# MD2_SE_Main_rev4_1.net
KiCad netlist of a schematic drawn in EAGLE
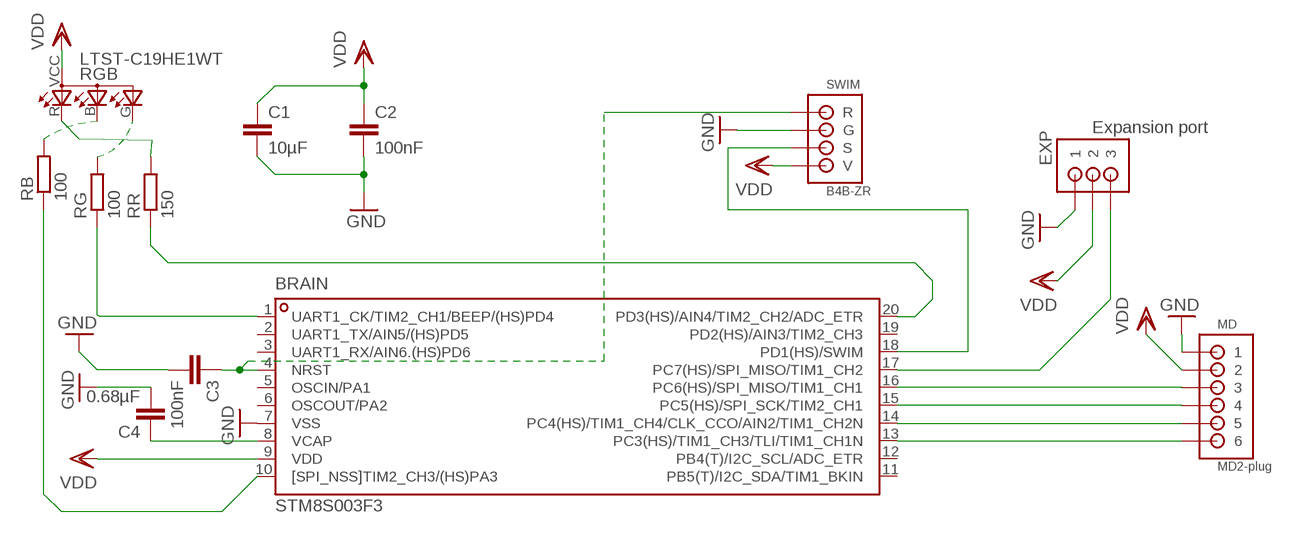
[diagram p0: schematic, sheet 1]

(export (version "E")
  (design (tool "Eeschema 10.0.6"))
  (components
    (comp (ref "BRAIN")
      (value "STM8S003F3")
      (footprint "eagle-import:TSSOP20")
      (libsource (lib "eagle-import") (part "STM8S003F3"))
    )
    (comp (ref "C1")
      (value "10µF")
      (footprint "eagle-import:C0603K")
      (libsource (lib "eagle-import") (part "C-EUC0603K"))
    )
    (comp (ref "C2")
      (value "100nF")
      (footprint "eagle-import:C0603K")
      (libsource (lib "eagle-import") (part "C-EUC0603K"))
    )
    (comp (ref "C3")
      (value "100nF")
      (footprint "eagle-import:C0603K")
      (libsource (lib "eagle-import") (part "C-EUC0603K"))
    )
    (comp (ref "C4")
      (value "0.68µF")
      (footprint "eagle-import:C0603K")
      (libsource (lib "eagle-import") (part "C-EUC0603K"))
    )
    (comp (ref "EXP")
      (value "Expansion port")
      (footprint "eagle-import:B3B-ZR")
      (libsource (lib "eagle-import") (part "B3B-ZR"))
    )
    (comp (ref "MD")
      (value "MD2-plug")
      (footprint "eagle-import:B6B-ZR")
      (libsource (lib "eagle-import") (part "B6B-ZR"))
    )
    (comp (ref "RB")
      (value "100")
      (footprint "eagle-import:R0603")
      (libsource (lib "eagle-import") (part "R-EU_R0603"))
    )
    (comp (ref "RG")
      (value "100")
      (footprint "eagle-import:R0603")
      (libsource (lib "eagle-import") (part "R-EU_R0603"))
    )
    (comp (ref "RGB")
      (value "LTST-C19HE1WT")
      (footprint "eagle-import:0606")
      (libsource (lib "eagle-import") (part "LTST-C19HE1WT"))
    )
    (comp (ref "RR")
      (value "150")
      (footprint "eagle-import:R0603")
      (libsource (lib "eagle-import") (part "R-EU_R0603"))
    )
    (comp (ref "SWIM")
      (value "B4B-ZR")
      (footprint "eagle-import:B4B-ZR")
      (libsource (lib "eagle-import") (part "B4B-ZR"))
    )
  )
  (nets
    (net (code "1") (name "GND") (class "Default")
      (node (ref "BRAIN") (pin "7") (pinfunction "VSS_7") (pintype "bidirectional"))
      (node (ref "C1") (pin "2") (pinfunction "2_2") (pintype "passive"))
      (node (ref "C2") (pin "2") (pinfunction "2_2") (pintype "passive"))
      (node (ref "C3") (pin "2") (pinfunction "2_2") (pintype "passive"))
      (node (ref "C4") (pin "2") (pinfunction "2_2") (pintype "passive"))
      (node (ref "EXP") (pin "1") (pinfunction "1_1") (pintype "bidirectional"))
      (node (ref "MD") (pin "1") (pinfunction "1_1") (pintype "bidirectional"))
      (node (ref "SWIM") (pin "GND") (pinfunction "G_GND") (pintype "bidirectional"))
    )
    (net (code "2") (name "Net-(BRAIN-NRST)") (class "Default")
      (node (ref "BRAIN") (pin "4") (pinfunction "NRST_4") (pintype "input"))
      (node (ref "C3") (pin "1") (pinfunction "1_1") (pintype "passive"))
      (node (ref "SWIM") (pin "RST") (pinfunction "R_RST") (pintype "bidirectional"))
    )
    (net (code "3") (name "Net-(BRAIN-PC3(HS){slash}TIM1_CH3{slash}TLI{slash}TIM1_CH1N)") (class "Default")
      (node (ref "BRAIN") (pin "13") (pinfunction "PC3(HS)/TIM1_CH3/TLI/TIM1_CH1N_13") (pintype "bidirectional"))
      (node (ref "MD") (pin "6") (pinfunction "6_6") (pintype "bidirectional"))
    )
    (net (code "4") (name "Net-(BRAIN-PC4(HS){slash}TIM1_CH4{slash}CLK_CCO{slash}AIN2{slash}TIM1_CH2N)") (class "Default")
      (node (ref "BRAIN") (pin "14") (pinfunction "PC4(HS)/TIM1_CH4/CLK_CCO/AIN2/TIM1_CH2N_14") (pintype "bidirectional"))
      (node (ref "MD") (pin "5") (pinfunction "5_5") (pintype "bidirectional"))
    )
    (net (code "5") (name "Net-(BRAIN-PC5(HS){slash}SPI_SCK{slash}TIM2_CH1)") (class "Default")
      (node (ref "BRAIN") (pin "15") (pinfunction "PC5(HS)/SPI_SCK/TIM2_CH1_15") (pintype "bidirectional"))
      (node (ref "MD") (pin "4") (pinfunction "4_4") (pintype "bidirectional"))
    )
    (net (code "6") (name "Net-(BRAIN-PC6(HS){slash}SPI_MISO{slash}TIM1_CH1)") (class "Default")
      (node (ref "BRAIN") (pin "16") (pinfunction "PC6(HS)/SPI_MISO/TIM1_CH1_16") (pintype "bidirectional"))
      (node (ref "MD") (pin "3") (pinfunction "3_3") (pintype "bidirectional"))
    )
    (net (code "7") (name "Net-(BRAIN-PC7(HS){slash}SPI_MISO{slash}TIM1_CH2)") (class "Default")
      (node (ref "BRAIN") (pin "17") (pinfunction "PC7(HS)/SPI_MISO/TIM1_CH2_17") (pintype "bidirectional"))
      (node (ref "EXP") (pin "3") (pinfunction "3_3") (pintype "bidirectional"))
    )
    (net (code "8") (name "Net-(BRAIN-PD1(HS){slash}SWIM)") (class "Default")
      (node (ref "BRAIN") (pin "18") (pinfunction "PD1(HS)/SWIM_18") (pintype "bidirectional"))
      (node (ref "SWIM") (pin "SWIM") (pinfunction "S_SWIM") (pintype "bidirectional"))
    )
    (net (code "9") (name "Net-(BRAIN-PD3(HS){slash}AIN4{slash}TIM2_CH2{slash}ADC_ETR)") (class "Default")
      (node (ref "BRAIN") (pin "20") (pinfunction "PD3(HS)/AIN4/TIM2_CH2/ADC_ETR_20") (pintype "bidirectional"))
      (node (ref "RR") (pin "1") (pinfunction "1_1") (pintype "passive"))
    )
    (net (code "10") (name "Net-(BRAIN-UART1_CK{slash}TIM2_CH1{slash}BEEP{slash}(HS)PD4)") (class "Default")
      (node (ref "BRAIN") (pin "1") (pinfunction "UART1_CK/TIM2_CH1/BEEP/(HS)PD4_1") (pintype "bidirectional"))
      (node (ref "RG") (pin "1") (pinfunction "1_1") (pintype "passive"))
    )
    (net (code "11") (name "Net-(BRAIN-VCAP)") (class "Default")
      (node (ref "BRAIN") (pin "8") (pinfunction "VCAP_8") (pintype "bidirectional"))
      (node (ref "C4") (pin "1") (pinfunction "1_1") (pintype "passive"))
    )
    (net (code "12") (name "Net-(BRAIN-[SPI_NSS]TIM2_CH3{slash}(HS)PA3)") (class "Default")
      (node (ref "BRAIN") (pin "10") (pinfunction "[SPI_NSS]TIM2_CH3/(HS)PA3_10") (pintype "bidirectional"))
      (node (ref "RB") (pin "1") (pinfunction "1_1") (pintype "passive"))
    )
    (net (code "13") (name "Net-(RGB-CBLUE)") (class "Default")
      (node (ref "RB") (pin "2") (pinfunction "2_2") (pintype "passive"))
      (node (ref "RGB") (pin "B") (pinfunction "CBLUE_B") (pintype "passive"))
    )
    (net (code "14") (name "Net-(RGB-CGREEN)") (class "Default")
      (node (ref "RG") (pin "2") (pinfunction "2_2") (pintype "passive"))
      (node (ref "RGB") (pin "G") (pinfunction "CGREEN_G") (pintype "passive"))
    )
    (net (code "15") (name "Net-(RGB-CRED)") (class "Default")
      (node (ref "RGB") (pin "R") (pinfunction "CRED_R") (pintype "passive"))
      (node (ref "RR") (pin "2") (pinfunction "2_2") (pintype "passive"))
    )
    (net (code "16") (name "VDD") (class "Default")
      (node (ref "BRAIN") (pin "9") (pinfunction "VDD_9") (pintype "power_in"))
      (node (ref "C1") (pin "1") (pinfunction "1_1") (pintype "passive"))
      (node (ref "C2") (pin "1") (pinfunction "1_1") (pintype "passive"))
      (node (ref "EXP") (pin "2") (pinfunction "2_2") (pintype "bidirectional"))
      (node (ref "MD") (pin "2") (pinfunction "2_2") (pintype "bidirectional"))
      (node (ref "RGB") (pin "VCC") (pinfunction "V+_VCC") (pintype "passive"))
      (node (ref "SWIM") (pin "VDD") (pinfunction "V_VDD") (pintype "bidirectional"))
    )
    (net (code "17") (name "unconnected-(BRAIN-OSCIN{slash}PA1-Pad5)") (class "Default")
      (node (ref "BRAIN") (pin "5") (pinfunction "OSCIN/PA1_5") (pintype "bidirectional"))
    )
    (net (code "18") (name "unconnected-(BRAIN-OSCOUT{slash}PA2-Pad6)") (class "Default")
      (node (ref "BRAIN") (pin "6") (pinfunction "OSCOUT/PA2_6") (pintype "bidirectional"))
    )
    (net (code "19") (name "unconnected-(BRAIN-PB4(T){slash}I2C_SCL{slash}ADC_ETR-Pad12)") (class "Default")
      (node (ref "BRAIN") (pin "12") (pinfunction "PB4(T)/I2C_SCL/ADC_ETR_12") (pintype "bidirectional"))
    )
    (net (code "20") (name "unconnected-(BRAIN-PB5(T){slash}I2C_SDA{slash}TIM1_BKIN-Pad11)") (class "Default")
      (node (ref "BRAIN") (pin "11") (pinfunction "PB5(T)/I2C_SDA/TIM1_BKIN_11") (pintype "bidirectional"))
    )
    (net (code "21") (name "unconnected-(BRAIN-PD2(HS){slash}AIN3{slash}TIM2_CH3-Pad19)") (class "Default")
      (node (ref "BRAIN") (pin "19") (pinfunction "PD2(HS)/AIN3/TIM2_CH3_19") (pintype "bidirectional"))
    )
    (net (code "22") (name "unconnected-(BRAIN-UART1_RX{slash}AIN6.(HS)PD6-Pad3)") (class "Default")
      (node (ref "BRAIN") (pin "3") (pinfunction "UART1_RX/AIN6.(HS)PD6_3") (pintype "bidirectional"))
    )
    (net (code "23") (name "unconnected-(BRAIN-UART1_TX{slash}AIN5{slash}(HS)PD5-Pad2)") (class "Default")
      (node (ref "BRAIN") (pin "2") (pinfunction "UART1_TX/AIN5/(HS)PD5_2") (pintype "bidirectional"))
    )
  )
)
